# Orion-BOTTOM.net
KiCad netlist of a schematic drawn in EAGLE
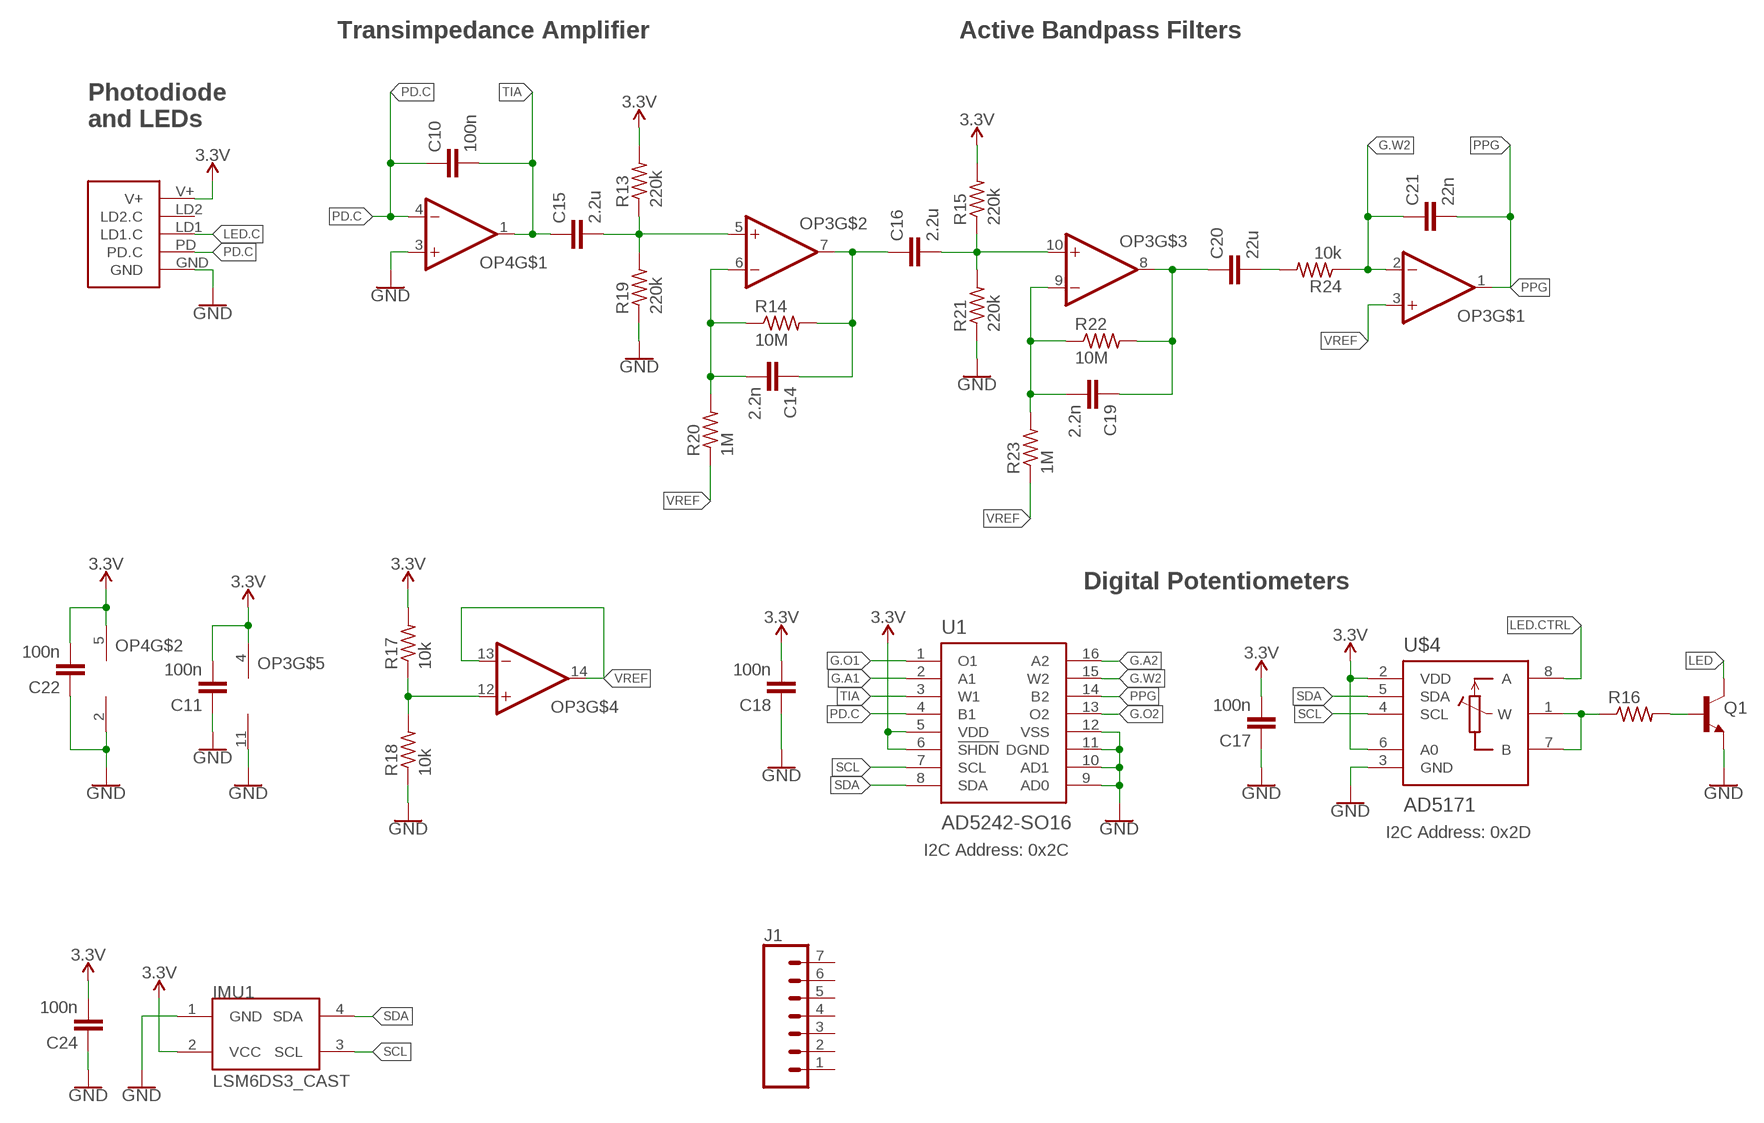
[diagram p0: schematic, sheet 1]

(export (version "E")
  (design (tool "Eeschema 10.0.6"))
  (components
    (comp (ref "C10")
      (value "100n")
      (footprint "eagle-import:C0603")
      (libsource (lib "eagle-import") (part "CAPACITOR0603"))
    )
    (comp (ref "C11")
      (value "100n")
      (footprint "eagle-import:C0603")
      (libsource (lib "eagle-import") (part "CAPACITOR0603"))
    )
    (comp (ref "C14")
      (value "2.2n")
      (footprint "eagle-import:C0603")
      (libsource (lib "eagle-import") (part "CAPACITOR0603"))
    )
    (comp (ref "C15")
      (value "2.2u")
      (footprint "eagle-import:C0603")
      (libsource (lib "eagle-import") (part "CAPACITOR0603"))
    )
    (comp (ref "C16")
      (value "2.2u")
      (footprint "eagle-import:C0603")
      (libsource (lib "eagle-import") (part "CAPACITOR0603"))
    )
    (comp (ref "C17")
      (value "100n")
      (footprint "eagle-import:C0603")
      (libsource (lib "eagle-import") (part "CAPACITOR0603"))
    )
    (comp (ref "C18")
      (value "100n")
      (footprint "eagle-import:C0603")
      (libsource (lib "eagle-import") (part "CAPACITOR0603"))
    )
    (comp (ref "C19")
      (value "2.2n")
      (footprint "eagle-import:C0603")
      (libsource (lib "eagle-import") (part "CAPACITOR0603"))
    )
    (comp (ref "C20")
      (value "22u")
      (footprint "eagle-import:C0603")
      (libsource (lib "eagle-import") (part "CAPACITOR0603"))
    )
    (comp (ref "C21")
      (value "22n")
      (footprint "eagle-import:C0603")
      (libsource (lib "eagle-import") (part "CAPACITOR0603"))
    )
    (comp (ref "C22")
      (value "100n")
      (footprint "eagle-import:C0603")
      (libsource (lib "eagle-import") (part "CAPACITOR0603"))
    )
    (comp (ref "C24")
      (value "100n")
      (footprint "eagle-import:C0603")
      (libsource (lib "eagle-import") (part "CAPACITOR0603"))
    )
    (comp (ref "IMU1")
      (value "LSM6DS3_CAST")
      (footprint "eagle-import:LSM6DS3_CAST")
      (libsource (lib "eagle-import") (part "LSM6DS3_CAST"))
    )
    (comp (ref "J1")
      (value "CONN_07")
      (footprint "eagle-import:1X07")
      (libsource (lib "eagle-import") (part "CONN_07"))
    )
    (comp (ref "OP3")
      (value "OP-QUAD-SO14")
      (footprint "eagle-import:SO14")
      (libsource (lib "eagle-import") (part "OP-QUAD-SO14"))
    )
    (comp (ref "OP4")
      (value "OP-SINGLEOT")
      (footprint "eagle-import:SOT23-5")
      (libsource (lib "eagle-import") (part "OP-SINGLEOT"))
    )
    (comp (ref "Q1")
      (value "NPN-GENERIC")
      (footprint "eagle-import:SOT23-3")
      (libsource (lib "eagle-import") (part "NPN-GENERIC"))
    )
    (comp (ref "R13")
      (value "220k")
      (footprint "eagle-import:R0603")
      (libsource (lib "eagle-import") (part "RESISTOR0603"))
    )
    (comp (ref "R14")
      (value "10M")
      (footprint "eagle-import:R0603")
      (libsource (lib "eagle-import") (part "RESISTOR0603"))
    )
    (comp (ref "R15")
      (value "220k")
      (footprint "eagle-import:R0603")
      (libsource (lib "eagle-import") (part "RESISTOR0603"))
    )
    (comp (ref "R16")
      (value "RESISTOR0603")
      (footprint "eagle-import:R0603")
      (libsource (lib "eagle-import") (part "RESISTOR0603"))
    )
    (comp (ref "R17")
      (value "10k")
      (footprint "eagle-import:R0402")
      (libsource (lib "eagle-import") (part "RESISTOR0402"))
    )
    (comp (ref "R18")
      (value "10k")
      (footprint "eagle-import:R0402")
      (libsource (lib "eagle-import") (part "RESISTOR0402"))
    )
    (comp (ref "R19")
      (value "220k")
      (footprint "eagle-import:R0603")
      (libsource (lib "eagle-import") (part "RESISTOR0603"))
    )
    (comp (ref "R20")
      (value "1M")
      (footprint "eagle-import:R0603")
      (libsource (lib "eagle-import") (part "RESISTOR0603"))
    )
    (comp (ref "R21")
      (value "220k")
      (footprint "eagle-import:R0603")
      (libsource (lib "eagle-import") (part "RESISTOR0603"))
    )
    (comp (ref "R22")
      (value "10M")
      (footprint "eagle-import:R0603")
      (libsource (lib "eagle-import") (part "RESISTOR0603"))
    )
    (comp (ref "R23")
      (value "1M")
      (footprint "eagle-import:R0603")
      (libsource (lib "eagle-import") (part "RESISTOR0603"))
    )
    (comp (ref "R24")
      (value "10k")
      (footprint "eagle-import:R0603")
      (libsource (lib "eagle-import") (part "RESISTOR0603"))
    )
    (comp (ref "U$3")
      (value "PPG.MODULE.2")
      (footprint "eagle-import:PPG.MODULE.2")
      (libsource (lib "eagle-import") (part "PPG.MODULE.2"))
    )
    (comp (ref "U$4")
      (value "AD5171")
      (footprint "eagle-import:SOT-23-8")
      (libsource (lib "eagle-import") (part "AD5171"))
    )
    (comp (ref "U1")
      (value "AD5242-SO16")
      (footprint "eagle-import:SO16")
      (libsource (lib "eagle-import") (part "AD5242-SO16"))
    )
  )
  (nets
    (net (code "1") (name "3.3V") (class "Default")
      (node (ref "C11") (pin "2") (pinfunction "2_2") (pintype "passive"))
      (node (ref "C17") (pin "2") (pinfunction "2_2") (pintype "passive"))
      (node (ref "C18") (pin "2") (pinfunction "2_2") (pintype "passive"))
      (node (ref "C22") (pin "2") (pinfunction "2_2") (pintype "passive"))
      (node (ref "C24") (pin "2") (pinfunction "2_2") (pintype "passive"))
      (node (ref "IMU1") (pin "2") (pinfunction "VCC_2") (pintype "bidirectional"))
      (node (ref "OP3") (pin "4") (pinfunction "V+_4") (pintype "power_in"))
      (node (ref "OP4") (pin "5") (pinfunction "V+_5") (pintype "power_in"))
      (node (ref "R13") (pin "2") (pinfunction "2_2") (pintype "passive"))
      (node (ref "R15") (pin "2") (pinfunction "2_2") (pintype "passive"))
      (node (ref "R17") (pin "2") (pinfunction "2_2") (pintype "passive"))
      (node (ref "U$3") (pin "V+") (pinfunction "V+_V+") (pintype "bidirectional"))
      (node (ref "U$4") (pin "2") (pinfunction "VDD_2") (pintype "bidirectional"))
      (node (ref "U$4") (pin "6") (pinfunction "A0_6") (pintype "bidirectional"))
      (node (ref "U1") (pin "5") (pinfunction "VDD_5") (pintype "bidirectional"))
      (node (ref "U1") (pin "6") (pinfunction "~{SHDN}_6") (pintype "bidirectional"))
    )
    (net (code "2") (name "G.A1") (class "Default")
      (node (ref "U1") (pin "2") (pinfunction "A1_2") (pintype "bidirectional"))
    )
    (net (code "3") (name "G.A2") (class "Default")
      (node (ref "U1") (pin "16") (pinfunction "A2_16") (pintype "bidirectional"))
    )
    (net (code "4") (name "G.O1") (class "Default")
      (node (ref "U1") (pin "1") (pinfunction "O1_1") (pintype "bidirectional"))
    )
    (net (code "5") (name "G.O2") (class "Default")
      (node (ref "U1") (pin "13") (pinfunction "O2_13") (pintype "bidirectional"))
    )
    (net (code "6") (name "G.W2") (class "Default")
      (node (ref "C21") (pin "1") (pinfunction "1_1") (pintype "passive"))
      (node (ref "OP3") (pin "2") (pinfunction "-IN_2") (pintype "input"))
      (node (ref "R24") (pin "1") (pinfunction "1_1") (pintype "passive"))
      (node (ref "U1") (pin "15") (pinfunction "W2_15") (pintype "bidirectional"))
    )
    (net (code "7") (name "GND") (class "Default")
      (node (ref "C11") (pin "1") (pinfunction "1_1") (pintype "passive"))
      (node (ref "C17") (pin "1") (pinfunction "1_1") (pintype "passive"))
      (node (ref "C18") (pin "1") (pinfunction "1_1") (pintype "passive"))
      (node (ref "C22") (pin "1") (pinfunction "1_1") (pintype "passive"))
      (node (ref "C24") (pin "1") (pinfunction "1_1") (pintype "passive"))
      (node (ref "IMU1") (pin "1") (pinfunction "GND_1") (pintype "bidirectional"))
      (node (ref "OP3") (pin "11") (pinfunction "V-_11") (pintype "power_in"))
      (node (ref "OP4") (pin "2") (pinfunction "V-_2") (pintype "power_in"))
      (node (ref "OP4") (pin "3") (pinfunction "+IN_3") (pintype "input"))
      (node (ref "Q1") (pin "2") (pinfunction "E_2") (pintype "passive"))
      (node (ref "R18") (pin "1") (pinfunction "1_1") (pintype "passive"))
      (node (ref "R19") (pin "1") (pinfunction "1_1") (pintype "passive"))
      (node (ref "R21") (pin "1") (pinfunction "1_1") (pintype "passive"))
      (node (ref "U$3") (pin "GND") (pinfunction "GND_GND") (pintype "bidirectional"))
      (node (ref "U$4") (pin "3") (pinfunction "GND_3") (pintype "bidirectional"))
      (node (ref "U1") (pin "10") (pinfunction "AD1_10") (pintype "bidirectional"))
      (node (ref "U1") (pin "11") (pinfunction "DGND_11") (pintype "bidirectional"))
      (node (ref "U1") (pin "12") (pinfunction "VSS_12") (pintype "bidirectional"))
      (node (ref "U1") (pin "9") (pinfunction "AD0_9") (pintype "bidirectional"))
    )
    (net (code "8") (name "LED") (class "Default")
      (node (ref "Q1") (pin "3") (pinfunction "C_3") (pintype "passive"))
    )
    (net (code "9") (name "LED.C") (class "Default")
      (node (ref "U$3") (pin "LD1") (pinfunction "LD1.C_LD1") (pintype "bidirectional"))
    )
    (net (code "10") (name "LED.CTRL") (class "Default")
      (node (ref "U$4") (pin "8") (pinfunction "A_8") (pintype "bidirectional"))
    )
    (net (code "11") (name "Net-(C20-Pad2)") (class "Default")
      (node (ref "C20") (pin "2") (pinfunction "2_2") (pintype "passive"))
      (node (ref "R24") (pin "2") (pinfunction "2_2") (pintype "passive"))
    )
    (net (code "12") (name "Net-(OP3B-+IN)") (class "Default")
      (node (ref "C15") (pin "2") (pinfunction "2_2") (pintype "passive"))
      (node (ref "OP3") (pin "5") (pinfunction "+IN_5") (pintype "input"))
      (node (ref "R13") (pin "1") (pinfunction "1_1") (pintype "passive"))
      (node (ref "R19") (pin "2") (pinfunction "2_2") (pintype "passive"))
    )
    (net (code "13") (name "Net-(OP3B--IN)") (class "Default")
      (node (ref "C14") (pin "2") (pinfunction "2_2") (pintype "passive"))
      (node (ref "OP3") (pin "6") (pinfunction "-IN_6") (pintype "input"))
      (node (ref "R14") (pin "1") (pinfunction "1_1") (pintype "passive"))
      (node (ref "R20") (pin "2") (pinfunction "2_2") (pintype "passive"))
    )
    (net (code "14") (name "Net-(OP3B-OUT)") (class "Default")
      (node (ref "C14") (pin "1") (pinfunction "1_1") (pintype "passive"))
      (node (ref "C16") (pin "1") (pinfunction "1_1") (pintype "passive"))
      (node (ref "OP3") (pin "7") (pinfunction "OUT_7") (pintype "output"))
      (node (ref "R14") (pin "2") (pinfunction "2_2") (pintype "passive"))
    )
    (net (code "15") (name "Net-(OP3C-+IN)") (class "Default")
      (node (ref "C16") (pin "2") (pinfunction "2_2") (pintype "passive"))
      (node (ref "OP3") (pin "10") (pinfunction "+IN_10") (pintype "input"))
      (node (ref "R15") (pin "1") (pinfunction "1_1") (pintype "passive"))
      (node (ref "R21") (pin "2") (pinfunction "2_2") (pintype "passive"))
    )
    (net (code "16") (name "Net-(OP3C--IN)") (class "Default")
      (node (ref "C19") (pin "2") (pinfunction "2_2") (pintype "passive"))
      (node (ref "OP3") (pin "9") (pinfunction "-IN_9") (pintype "input"))
      (node (ref "R22") (pin "1") (pinfunction "1_1") (pintype "passive"))
      (node (ref "R23") (pin "2") (pinfunction "2_2") (pintype "passive"))
    )
    (net (code "17") (name "Net-(OP3C-OUT)") (class "Default")
      (node (ref "C19") (pin "1") (pinfunction "1_1") (pintype "passive"))
      (node (ref "C20") (pin "1") (pinfunction "1_1") (pintype "passive"))
      (node (ref "OP3") (pin "8") (pinfunction "OUT_8") (pintype "output"))
      (node (ref "R22") (pin "2") (pinfunction "2_2") (pintype "passive"))
    )
    (net (code "18") (name "Net-(OP3D-+IN)") (class "Default")
      (node (ref "OP3") (pin "12") (pinfunction "+IN_12") (pintype "input"))
      (node (ref "R17") (pin "1") (pinfunction "1_1") (pintype "passive"))
      (node (ref "R18") (pin "2") (pinfunction "2_2") (pintype "passive"))
    )
    (net (code "19") (name "Net-(Q1-B)") (class "Default")
      (node (ref "Q1") (pin "1") (pinfunction "B_1") (pintype "passive"))
      (node (ref "R16") (pin "2") (pinfunction "2_2") (pintype "passive"))
    )
    (net (code "20") (name "Net-(U$4-B)") (class "Default")
      (node (ref "R16") (pin "1") (pinfunction "1_1") (pintype "passive"))
      (node (ref "U$4") (pin "1") (pinfunction "W_1") (pintype "bidirectional"))
      (node (ref "U$4") (pin "7") (pinfunction "B_7") (pintype "bidirectional"))
    )
    (net (code "21") (name "PD.C") (class "Default")
      (node (ref "C10") (pin "1") (pinfunction "1_1") (pintype "passive"))
      (node (ref "OP4") (pin "4") (pinfunction "-IN_4") (pintype "input"))
      (node (ref "U$3") (pin "PD") (pinfunction "PD.C_PD") (pintype "bidirectional"))
      (node (ref "U1") (pin "4") (pinfunction "B1_4") (pintype "bidirectional"))
    )
    (net (code "22") (name "PPG") (class "Default")
      (node (ref "C21") (pin "2") (pinfunction "2_2") (pintype "passive"))
      (node (ref "OP3") (pin "1") (pinfunction "OUT_1") (pintype "output"))
      (node (ref "U1") (pin "14") (pinfunction "B2_14") (pintype "bidirectional"))
    )
    (net (code "23") (name "SCL") (class "Default")
      (node (ref "IMU1") (pin "3") (pinfunction "SCL_3") (pintype "bidirectional"))
      (node (ref "U$4") (pin "4") (pinfunction "SCL_4") (pintype "bidirectional"))
      (node (ref "U1") (pin "7") (pinfunction "SCL_7") (pintype "bidirectional"))
    )
    (net (code "24") (name "SDA") (class "Default")
      (node (ref "IMU1") (pin "4") (pinfunction "SDA_4") (pintype "bidirectional"))
      (node (ref "U$4") (pin "5") (pinfunction "SDA_5") (pintype "bidirectional"))
      (node (ref "U1") (pin "8") (pinfunction "SDA_8") (pintype "bidirectional"))
    )
    (net (code "25") (name "TIA") (class "Default")
      (node (ref "C10") (pin "2") (pinfunction "2_2") (pintype "passive"))
      (node (ref "C15") (pin "1") (pinfunction "1_1") (pintype "passive"))
      (node (ref "OP4") (pin "1") (pinfunction "OUT_1") (pintype "output"))
      (node (ref "U1") (pin "3") (pinfunction "W1_3") (pintype "bidirectional"))
    )
    (net (code "26") (name "VREF") (class "Default")
      (node (ref "OP3") (pin "13") (pinfunction "-IN_13") (pintype "input"))
      (node (ref "OP3") (pin "14") (pinfunction "OUT_14") (pintype "output"))
      (node (ref "OP3") (pin "3") (pinfunction "+IN_3") (pintype "input"))
      (node (ref "R20") (pin "1") (pinfunction "1_1") (pintype "passive"))
      (node (ref "R23") (pin "1") (pinfunction "1_1") (pintype "passive"))
    )
    (net (code "27") (name "unconnected-(J1-Pad1)") (class "Default")
      (node (ref "J1") (pin "1") (pinfunction "1_1") (pintype "passive"))
    )
    (net (code "28") (name "unconnected-(J1-Pad2)") (class "Default")
      (node (ref "J1") (pin "2") (pinfunction "2_2") (pintype "passive"))
    )
    (net (code "29") (name "unconnected-(J1-Pad3)") (class "Default")
      (node (ref "J1") (pin "3") (pinfunction "3_3") (pintype "passive"))
    )
    (net (code "30") (name "unconnected-(J1-Pad4)") (class "Default")
      (node (ref "J1") (pin "4") (pinfunction "4_4") (pintype "passive"))
    )
    (net (code "31") (name "unconnected-(J1-Pad5)") (class "Default")
      (node (ref "J1") (pin "5") (pinfunction "5_5") (pintype "passive"))
    )
    (net (code "32") (name "unconnected-(J1-Pad6)") (class "Default")
      (node (ref "J1") (pin "6") (pinfunction "6_6") (pintype "passive"))
    )
    (net (code "33") (name "unconnected-(J1-Pad7)") (class "Default")
      (node (ref "J1") (pin "7") (pinfunction "7_7") (pintype "passive"))
    )
    (net (code "34") (name "unconnected-(U$3-LD2.C-PadLD2)") (class "Default")
      (node (ref "U$3") (pin "LD2") (pinfunction "LD2.C_LD2") (pintype "bidirectional"))
    )
  )
)
